# Heater_conflict-20171026-173219.net
KiCad netlist of a schematic drawn in Altium Designer
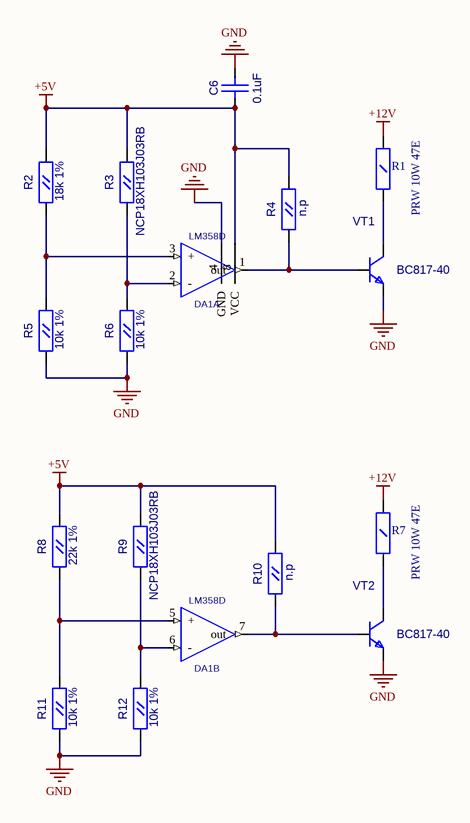
[diagram p0: Heater_conflict-20171026-173219.SchDoc]

(export (version "E")
  (design (tool "Eeschema 10.0.6"))
  (components
    (comp (ref "C6")
      (value "0.1uF")
      (footprint "CC0603")
      (description "CC0603")
      (libsource (lib "gprs_modem_2") (part "CC0603"))
    )
    (comp (ref "DA1") (value "LM358D") (footprint "SO-8") (libsource (lib "Schetchik") (part "LM358D")))
    (comp (ref "R1")
      (value "PRW 10W 47E")
      (footprint "R_5W_Cement")
      (libsource (lib "gprs_modem_2") (part "R_10W"))
    )
    (comp (ref "R2")
      (value "18k 1%")
      (footprint "RC0603")
      (description "RC0603")
      (libsource (lib "gprs_modem_2") (part "RC0603"))
    )
    (comp (ref "R3")
      (value "NCP18XH103J03RB")
      (footprint "RC0603")
      (description "RC0603")
      (libsource (lib "gprs_modem_2") (part "RC0603"))
    )
    (comp (ref "R4")
      (value "n.p")
      (footprint "RC0603")
      (description "RC0603")
      (libsource (lib "gprs_modem_2") (part "RC0603"))
    )
    (comp (ref "R5")
      (value "10k 1%")
      (footprint "RC0603")
      (description "RC0603")
      (libsource (lib "gprs_modem_2") (part "RC0603"))
    )
    (comp (ref "R6")
      (value "10k 1%")
      (footprint "RC0603")
      (description "RC0603")
      (libsource (lib "gprs_modem_2") (part "RC0603"))
    )
    (comp (ref "R7")
      (value "PRW 10W 47E")
      (footprint "R_5W_Cement")
      (libsource (lib "gprs_modem_2") (part "R_10W"))
    )
    (comp (ref "R8")
      (value "22k 1%")
      (footprint "RC0603")
      (description "RC0603")
      (libsource (lib "gprs_modem_2") (part "RC0603"))
    )
    (comp (ref "R9")
      (value "NCP18XH103J03RB")
      (footprint "RC0603")
      (description "RC0603")
      (libsource (lib "gprs_modem_2") (part "RC0603"))
    )
    (comp (ref "R10")
      (value "n.p")
      (footprint "RC0603")
      (description "RC0603")
      (libsource (lib "gprs_modem_2") (part "RC0603"))
    )
    (comp (ref "R11")
      (value "10k 1%")
      (footprint "RC0603")
      (description "RC0603")
      (libsource (lib "gprs_modem_2") (part "RC0603"))
    )
    (comp (ref "R12")
      (value "10k 1%")
      (footprint "RC0603")
      (description "RC0603")
      (libsource (lib "gprs_modem_2") (part "RC0603"))
    )
    (comp (ref "VT1")
      (value "BC817-40")
      (footprint "SOT-23(123)")
      (description "NPN 500ma transistor")
      (libsource (lib "gprs_modem_2") (part "BC846BLT1"))
    )
    (comp (ref "VT2")
      (value "BC817-40")
      (footprint "SOT-23(123)")
      (description "NPN 500ma transistor")
      (libsource (lib "gprs_modem_2") (part "BC846BLT1"))
    )
  )
  (nets
    (net (code "1") (name "+5V") (class "Default")
      (node (ref "C6") (pin "1") (pinfunction "A_1") (pintype "passive"))
      (node (ref "DA1") (pin "8") (pinfunction "VCC_8") (pintype "power_in"))
      (node (ref "R10") (pin "2") (pinfunction "B_2") (pintype "passive"))
      (node (ref "R2") (pin "2") (pinfunction "B_2") (pintype "passive"))
      (node (ref "R3") (pin "2") (pinfunction "B_2") (pintype "passive"))
      (node (ref "R4") (pin "2") (pinfunction "B_2") (pintype "passive"))
      (node (ref "R8") (pin "2") (pinfunction "B_2") (pintype "passive"))
      (node (ref "R9") (pin "2") (pinfunction "B_2") (pintype "passive"))
    )
    (net (code "2") (name "+12V") (class "Default")
      (node (ref "R1") (pin "2") (pinfunction "B_2") (pintype "passive"))
      (node (ref "R7") (pin "2") (pinfunction "B_2") (pintype "passive"))
    )
    (net (code "3") (name "GND") (class "Default")
      (node (ref "C6") (pin "2") (pinfunction "B_2") (pintype "passive"))
      (node (ref "DA1") (pin "4") (pinfunction "GND_4") (pintype "power_in"))
      (node (ref "R11") (pin "1") (pinfunction "A_1") (pintype "passive"))
      (node (ref "R12") (pin "1") (pinfunction "A_1") (pintype "passive"))
      (node (ref "R5") (pin "1") (pinfunction "A_1") (pintype "passive"))
      (node (ref "R6") (pin "1") (pinfunction "A_1") (pintype "passive"))
      (node (ref "VT1") (pin "2") (pinfunction "E_2") (pintype "passive"))
      (node (ref "VT2") (pin "2") (pinfunction "E_2") (pintype "passive"))
    )
    (net (code "4") (name "Net-(DA1A-+)") (class "Default")
      (node (ref "DA1") (pin "3") (pinfunction "+_3") (pintype "input"))
      (node (ref "R2") (pin "1") (pinfunction "A_1") (pintype "passive"))
      (node (ref "R5") (pin "2") (pinfunction "B_2") (pintype "passive"))
    )
    (net (code "5") (name "Net-(DA1A--)") (class "Default")
      (node (ref "DA1") (pin "2") (pinfunction "-_2") (pintype "input"))
      (node (ref "R3") (pin "1") (pinfunction "A_1") (pintype "passive"))
      (node (ref "R6") (pin "2") (pinfunction "B_2") (pintype "passive"))
    )
    (net (code "6") (name "Net-(DA1A-out)") (class "Default")
      (node (ref "DA1") (pin "1") (pinfunction "out_1") (pintype "output"))
      (node (ref "R4") (pin "1") (pinfunction "A_1") (pintype "passive"))
      (node (ref "VT1") (pin "1") (pinfunction "B_1") (pintype "passive"))
    )
    (net (code "7") (name "Net-(DA1B-+)") (class "Default")
      (node (ref "DA1") (pin "5") (pinfunction "+_5") (pintype "input"))
      (node (ref "R11") (pin "2") (pinfunction "B_2") (pintype "passive"))
      (node (ref "R8") (pin "1") (pinfunction "A_1") (pintype "passive"))
    )
    (net (code "8") (name "Net-(DA1B--)") (class "Default")
      (node (ref "DA1") (pin "6") (pinfunction "-_6") (pintype "input"))
      (node (ref "R12") (pin "2") (pinfunction "B_2") (pintype "passive"))
      (node (ref "R9") (pin "1") (pinfunction "A_1") (pintype "passive"))
    )
    (net (code "9") (name "Net-(DA1B-out)") (class "Default")
      (node (ref "DA1") (pin "7") (pinfunction "out_7") (pintype "output"))
      (node (ref "R10") (pin "1") (pinfunction "A_1") (pintype "passive"))
      (node (ref "VT2") (pin "1") (pinfunction "B_1") (pintype "passive"))
    )
    (net (code "10") (name "Net-(R1-A)") (class "Default")
      (node (ref "R1") (pin "1") (pinfunction "A_1") (pintype "passive"))
      (node (ref "VT1") (pin "3") (pinfunction "C_3") (pintype "passive"))
    )
    (net (code "11") (name "Net-(R7-A)") (class "Default")
      (node (ref "R7") (pin "1") (pinfunction "A_1") (pintype "passive"))
      (node (ref "VT2") (pin "3") (pinfunction "C_3") (pintype "passive"))
    )
  )
)
